# aduinobasic.net
KiCad netlist of a schematic drawn in EAGLE
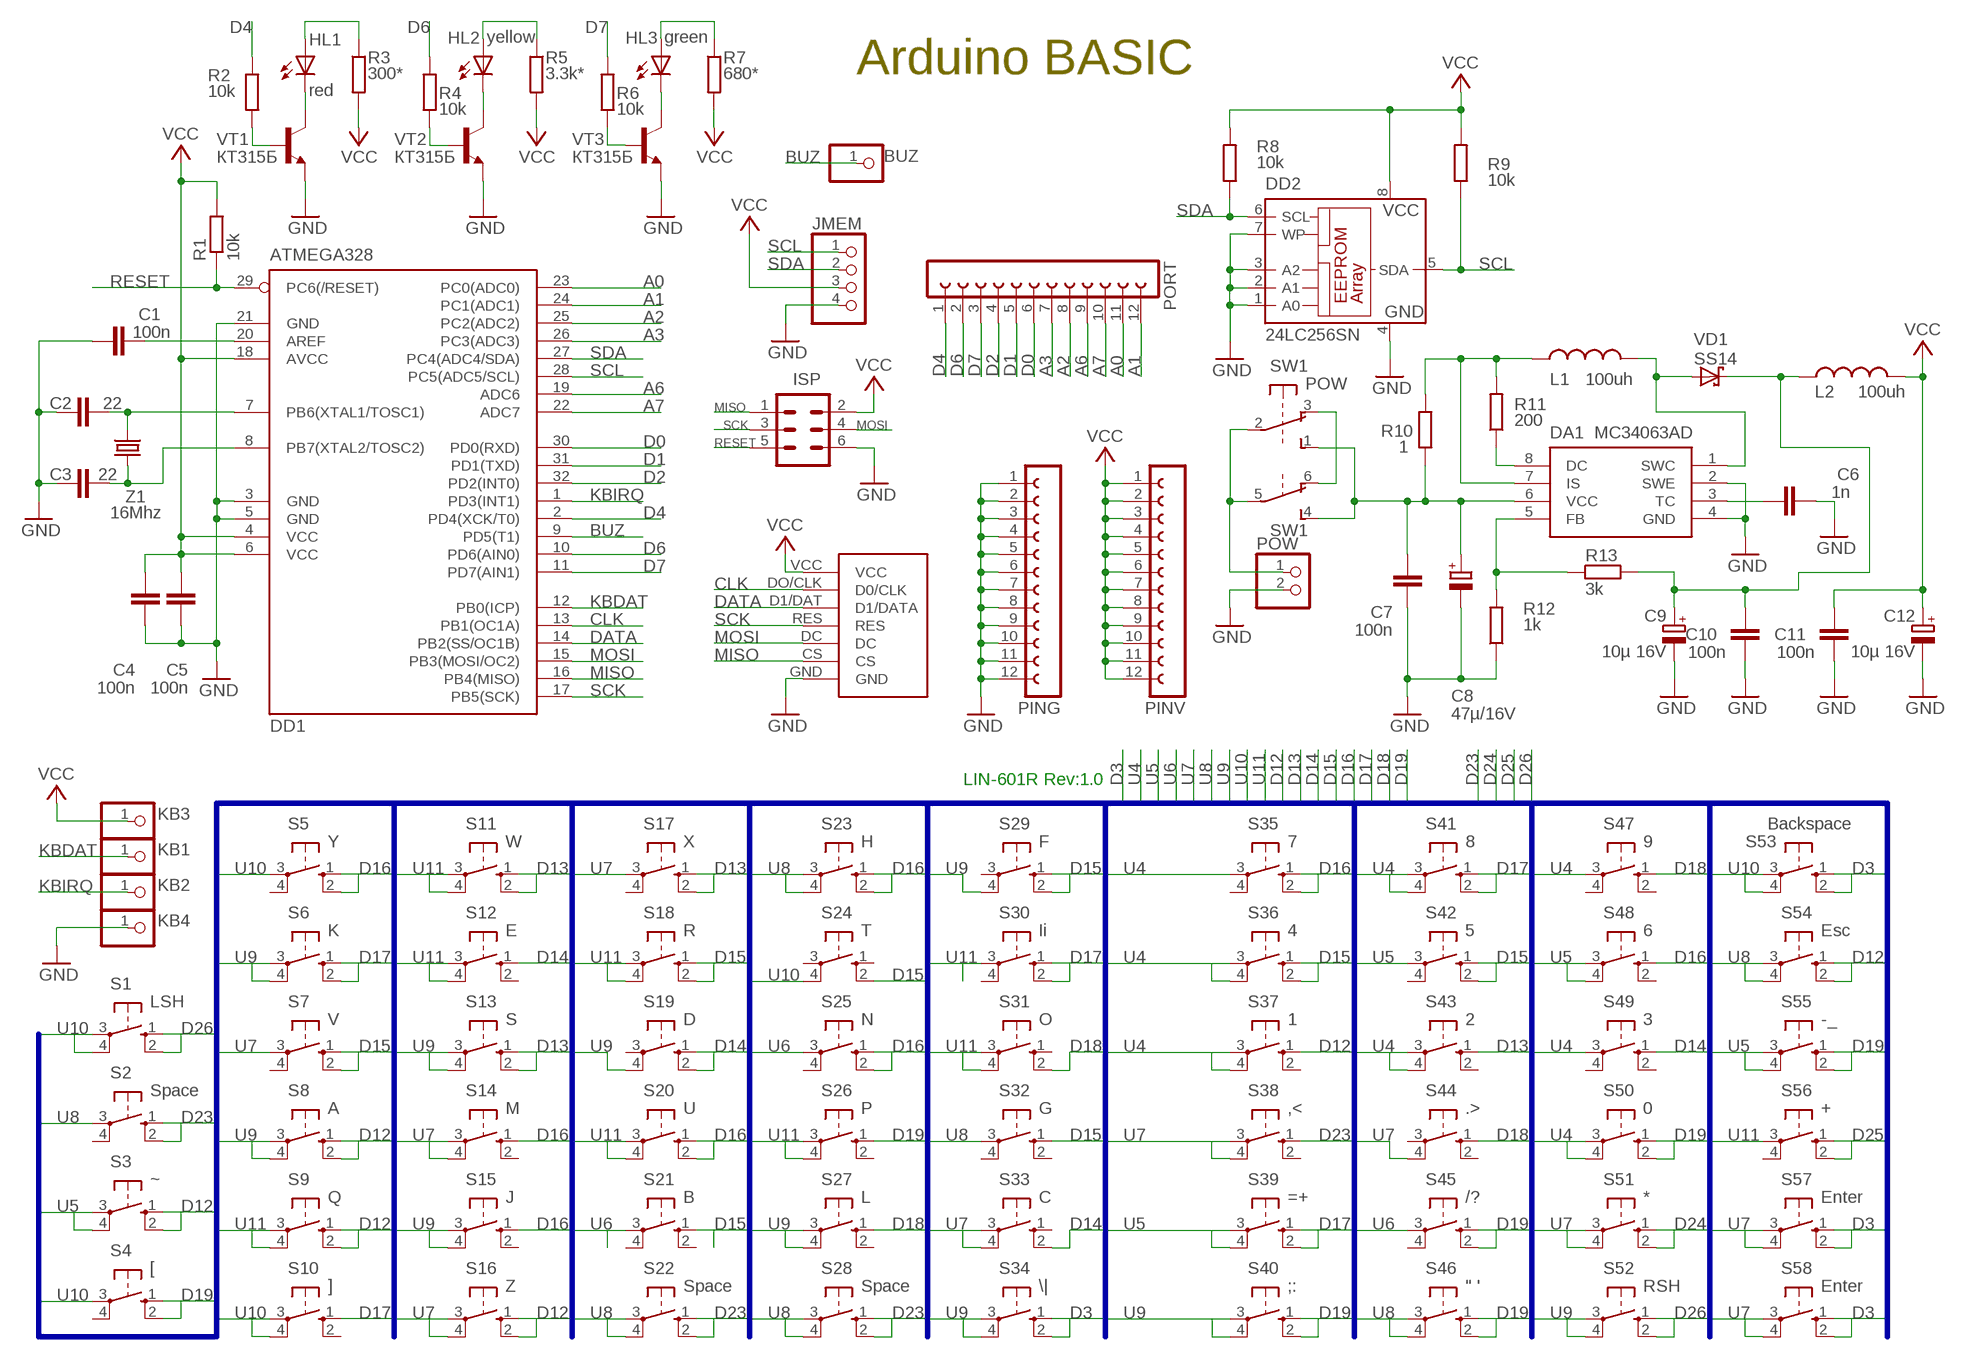
[diagram p0: schematic, sheet 1]

(export (version "E")
  (design (tool "Eeschema 10.0.6"))
  (components
    (comp (ref "BUZ")
      (value "PINHD-1X1")
      (footprint "eagle-import:1X01")
      (libsource (lib "eagle-import") (part "PINHD-1X1"))
    )
    (comp (ref "C1")
      (value "100n")
      (footprint "eagle-import:C0805")
      (libsource (lib "eagle-import") (part "rcl_C-EUC0805"))
    )
    (comp (ref "C2")
      (value "22")
      (footprint "eagle-import:C025-025X050")
      (libsource (lib "eagle-import") (part "rcl_C-EU025-025X050"))
    )
    (comp (ref "C3")
      (value "22")
      (footprint "eagle-import:C025-025X050")
      (libsource (lib "eagle-import") (part "rcl_C-EU025-025X050"))
    )
    (comp (ref "C4")
      (value "100n")
      (footprint "eagle-import:C0805")
      (libsource (lib "eagle-import") (part "rcl_C-EUC0805"))
    )
    (comp (ref "C5")
      (value "100n")
      (footprint "eagle-import:C0805")
      (libsource (lib "eagle-import") (part "rcl_C-EUC0805"))
    )
    (comp (ref "C6")
      (value "1n")
      (footprint "eagle-import:C025-025X050")
      (libsource (lib "eagle-import") (part "rcl_C-EU025-025X050"))
    )
    (comp (ref "C7")
      (value "100n")
      (footprint "eagle-import:C1206")
      (libsource (lib "eagle-import") (part "C-EUC1206"))
    )
    (comp (ref "C8")
      (value "47µ/16V")
      (footprint "eagle-import:RCL_E2-5")
      (libsource (lib "eagle-import") (part "RCL_CPOL-EUE2-5"))
    )
    (comp (ref "C9")
      (value "10µ 16V")
      (footprint "eagle-import:RCL_E2-5")
      (libsource (lib "eagle-import") (part "RCL_CPOL-EUE2-5"))
    )
    (comp (ref "C10")
      (value "100n")
      (footprint "eagle-import:C1206")
      (libsource (lib "eagle-import") (part "rcl_C-EUC1206"))
    )
    (comp (ref "C11")
      (value "100n")
      (footprint "eagle-import:C1206")
      (libsource (lib "eagle-import") (part "rcl_C-EUC1206"))
    )
    (comp (ref "C12")
      (value "10µ 16V")
      (footprint "eagle-import:RCL_E2-5")
      (libsource (lib "eagle-import") (part "RCL_CPOL-EUE2-5"))
    )
    (comp (ref "DA1")
      (value "MC34063AD")
      (footprint "eagle-import:SOIC8")
      (libsource (lib "eagle-import") (part "MC34063AD"))
    )
    (comp (ref "DD1")
      (value "ATMEGA328")
      (footprint "eagle-import:TQFP32-08")
      (fields (field (name "MPN") "ATMEGA8-16AU"))
      (libsource (lib "eagle-import") (part "MEGA8-AI"))
    )
    (comp (ref "DD2")
      (value "24LC256SN")
      (footprint "eagle-import:SO-08")
      (fields (field (name "MF") "MICROCHIP") (field (name "MPN") "24LC256-I/SN"))
      (libsource (lib "eagle-import") (part "24SNLC256"))
    )
    (comp (ref "DISPLAY")
      (value "SSD1306")
      (footprint "eagle-import:SSD1306_0.96")
      (libsource (lib "eagle-import") (part "SSD1306"))
    )
    (comp (ref "HL1")
      (value "red")
      (footprint "eagle-import:LED5MM")
      (libsource (lib "eagle-import") (part "LED5MM"))
    )
    (comp (ref "HL2")
      (value "yellow")
      (footprint "eagle-import:LED5MM")
      (libsource (lib "eagle-import") (part "LED5MM"))
    )
    (comp (ref "HL3")
      (value "green")
      (footprint "eagle-import:LED5MM")
      (libsource (lib "eagle-import") (part "LED5MM"))
    )
    (comp (ref "ISP")
      (value "MA03-2")
      (footprint "eagle-import:MA03-2")
      (libsource (lib "eagle-import") (part "MA03-2"))
    )
    (comp (ref "JMEM")
      (value "PINHD-1X4")
      (footprint "eagle-import:1X04")
      (libsource (lib "eagle-import") (part "PINHD-1X4"))
    )
    (comp (ref "KB1")
      (value "PINHD-1X1")
      (footprint "eagle-import:1X01")
      (libsource (lib "eagle-import") (part "PINHD-1X1"))
    )
    (comp (ref "KB2")
      (value "PINHD-1X1")
      (footprint "eagle-import:1X01")
      (libsource (lib "eagle-import") (part "PINHD-1X1"))
    )
    (comp (ref "KB3")
      (value "PINHD-1X1")
      (footprint "eagle-import:1X01")
      (libsource (lib "eagle-import") (part "PINHD-1X1"))
    )
    (comp (ref "KB4")
      (value "PINHD-1X1")
      (footprint "eagle-import:1X01")
      (libsource (lib "eagle-import") (part "PINHD-1X1"))
    )
    (comp (ref "L1")
      (value "100uh")
      (footprint "eagle-import:0207_10")
      (libsource (lib "eagle-import") (part "L-US0207/10"))
    )
    (comp (ref "L2")
      (value "100uh")
      (footprint "eagle-import:0204_5")
      (libsource (lib "eagle-import") (part "L-US0204/5"))
    )
    (comp (ref "PING")
      (value "FE12-1")
      (footprint "eagle-import:FE12")
      (fields (field (name "OC_FARNELL") "unknown") (field (name "OC_NEWARK") "unknown"))
      (libsource (lib "eagle-import") (part "FE12-1"))
    )
    (comp (ref "PINV")
      (value "FE12-1")
      (footprint "eagle-import:FE12")
      (fields (field (name "OC_FARNELL") "unknown") (field (name "OC_NEWARK") "unknown"))
      (libsource (lib "eagle-import") (part "FE12-1"))
    )
    (comp (ref "PORT")
      (value "FE12-1")
      (footprint "eagle-import:FE12")
      (fields (field (name "OC_FARNELL") "unknown") (field (name "OC_NEWARK") "unknown"))
      (libsource (lib "eagle-import") (part "FE12-1"))
    )
    (comp (ref "POW")
      (value "PINHD-1X2")
      (footprint "eagle-import:1X02")
      (libsource (lib "eagle-import") (part "PINHD-1X2"))
    )
    (comp (ref "R1")
      (value "10k")
      (footprint "eagle-import:R0805")
      (libsource (lib "eagle-import") (part "R-EU_R0805"))
    )
    (comp (ref "R2")
      (value "10k")
      (footprint "eagle-import:R0805")
      (libsource (lib "eagle-import") (part "R-EU_R0805"))
    )
    (comp (ref "R3")
      (value "300*")
      (footprint "eagle-import:R1206W")
      (libsource (lib "eagle-import") (part "R-EU_R1206W"))
    )
    (comp (ref "R4")
      (value "10k")
      (footprint "eagle-import:R0805")
      (libsource (lib "eagle-import") (part "R-EU_R0805"))
    )
    (comp (ref "R5")
      (value "3.3k*")
      (footprint "eagle-import:R1206W")
      (libsource (lib "eagle-import") (part "R-EU_R1206W"))
    )
    (comp (ref "R6")
      (value "10k")
      (footprint "eagle-import:R0805")
      (libsource (lib "eagle-import") (part "R-EU_R0805"))
    )
    (comp (ref "R7")
      (value "680*")
      (footprint "eagle-import:R0805")
      (libsource (lib "eagle-import") (part "R-EU_R0805"))
    )
    (comp (ref "R8")
      (value "10k")
      (footprint "eagle-import:R0805")
      (libsource (lib "eagle-import") (part "R-EU_R0805"))
    )
    (comp (ref "R9")
      (value "10k")
      (footprint "eagle-import:R0805")
      (libsource (lib "eagle-import") (part "R-EU_R0805"))
    )
    (comp (ref "R10")
      (value "1")
      (footprint "eagle-import:M1206")
      (libsource (lib "eagle-import") (part "R-EU_M1206"))
    )
    (comp (ref "R11")
      (value "200")
      (footprint "eagle-import:M1206")
      (libsource (lib "eagle-import") (part "R-EU_M1206"))
    )
    (comp (ref "R12")
      (value "1k")
      (footprint "eagle-import:M0805")
      (libsource (lib "eagle-import") (part "R-EU_M0805"))
    )
    (comp (ref "R13")
      (value "3k")
      (footprint "eagle-import:M0805")
      (libsource (lib "eagle-import") (part "R-EU_M0805"))
    )
    (comp (ref "S1")
      (value "LSH")
      (footprint "eagle-import:B3F-10XX")
      (fields (field (name "MPN") "B3F-1000"))
      (libsource (lib "eagle-import") (part "10-XX"))
    )
    (comp (ref "S2")
      (value "Space")
      (footprint "eagle-import:B3F-10XX")
      (fields (field (name "MPN") "B3F-1000"))
      (libsource (lib "eagle-import") (part "10-XX"))
    )
    (comp (ref "S3")
      (value "~")
      (footprint "eagle-import:B3F-10XX")
      (fields (field (name "MPN") "B3F-1000"))
      (libsource (lib "eagle-import") (part "10-XX"))
    )
    (comp (ref "S4")
      (value "[")
      (footprint "eagle-import:B3F-10XX")
      (fields (field (name "MPN") "B3F-1000"))
      (libsource (lib "eagle-import") (part "10-XX"))
    )
    (comp (ref "S5")
      (value "Y")
      (footprint "eagle-import:B3F-10XX")
      (fields (field (name "MPN") "B3F-1000"))
      (libsource (lib "eagle-import") (part "10-XX"))
    )
    (comp (ref "S6")
      (value "K")
      (footprint "eagle-import:B3F-10XX")
      (fields (field (name "MPN") "B3F-1000"))
      (libsource (lib "eagle-import") (part "10-XX"))
    )
    (comp (ref "S7")
      (value "V")
      (footprint "eagle-import:B3F-10XX")
      (fields (field (name "MPN") "B3F-1000"))
      (libsource (lib "eagle-import") (part "10-XX"))
    )
    (comp (ref "S8")
      (value "A")
      (footprint "eagle-import:B3F-10XX")
      (fields (field (name "MPN") "B3F-1000"))
      (libsource (lib "eagle-import") (part "10-XX"))
    )
    (comp (ref "S9")
      (value "Q")
      (footprint "eagle-import:B3F-10XX")
      (fields (field (name "MPN") "B3F-1000"))
      (libsource (lib "eagle-import") (part "10-XX"))
    )
    (comp (ref "S10")
      (value "]")
      (footprint "eagle-import:B3F-10XX")
      (fields (field (name "MPN") "B3F-1000"))
      (libsource (lib "eagle-import") (part "10-XX"))
    )
    (comp (ref "S11")
      (value "W")
      (footprint "eagle-import:B3F-10XX")
      (fields (field (name "MPN") "B3F-1000"))
      (libsource (lib "eagle-import") (part "10-XX"))
    )
    (comp (ref "S12")
      (value "E")
      (footprint "eagle-import:B3F-10XX")
      (fields (field (name "MPN") "B3F-1000"))
      (libsource (lib "eagle-import") (part "10-XX"))
    )
    (comp (ref "S13")
      (value "S")
      (footprint "eagle-import:B3F-10XX")
      (fields (field (name "MPN") "B3F-1000"))
      (libsource (lib "eagle-import") (part "10-XX"))
    )
    (comp (ref "S14")
      (value "M")
      (footprint "eagle-import:B3F-10XX")
      (fields (field (name "MPN") "B3F-1000"))
      (libsource (lib "eagle-import") (part "10-XX"))
    )
    (comp (ref "S15")
      (value "J")
      (footprint "eagle-import:B3F-10XX")
      (fields (field (name "MPN") "B3F-1000"))
      (libsource (lib "eagle-import") (part "10-XX"))
    )
    (comp (ref "S16")
      (value "Z")
      (footprint "eagle-import:B3F-10XX")
      (fields (field (name "MPN") "B3F-1000"))
      (libsource (lib "eagle-import") (part "10-XX"))
    )
    (comp (ref "S17")
      (value "X")
      (footprint "eagle-import:B3F-10XX")
      (fields (field (name "MPN") "B3F-1000"))
      (libsource (lib "eagle-import") (part "10-XX"))
    )
    (comp (ref "S18")
      (value "R")
      (footprint "eagle-import:B3F-10XX")
      (fields (field (name "MPN") "B3F-1000"))
      (libsource (lib "eagle-import") (part "10-XX"))
    )
    (comp (ref "S19")
      (value "D")
      (footprint "eagle-import:B3F-10XX")
      (fields (field (name "MPN") "B3F-1000"))
      (libsource (lib "eagle-import") (part "10-XX"))
    )
    (comp (ref "S20")
      (value "U")
      (footprint "eagle-import:B3F-10XX")
      (fields (field (name "MPN") "B3F-1000"))
      (libsource (lib "eagle-import") (part "10-XX"))
    )
    (comp (ref "S21")
      (value "B")
      (footprint "eagle-import:B3F-10XX")
      (fields (field (name "MPN") "B3F-1000"))
      (libsource (lib "eagle-import") (part "10-XX"))
    )
    (comp (ref "S22")
      (value "Space")
      (footprint "eagle-import:B3F-10XX")
      (fields (field (name "MPN") "B3F-1000"))
      (libsource (lib "eagle-import") (part "10-XX"))
    )
    (comp (ref "S23")
      (value "H")
      (footprint "eagle-import:B3F-10XX")
      (fields (field (name "MPN") "B3F-1000"))
      (libsource (lib "eagle-import") (part "10-XX"))
    )
    (comp (ref "S24")
      (value "T")
      (footprint "eagle-import:B3F-10XX")
      (fields (field (name "MPN") "B3F-1000"))
      (libsource (lib "eagle-import") (part "10-XX"))
    )
    (comp (ref "S25")
      (value "N")
      (footprint "eagle-import:B3F-10XX")
      (fields (field (name "MPN") "B3F-1000"))
      (libsource (lib "eagle-import") (part "10-XX"))
    )
    (comp (ref "S26")
      (value "P")
      (footprint "eagle-import:B3F-10XX")
      (fields (field (name "MPN") "B3F-1000"))
      (libsource (lib "eagle-import") (part "10-XX"))
    )
    (comp (ref "S27")
      (value "L")
      (footprint "eagle-import:B3F-10XX")
      (fields (field (name "MPN") "B3F-1000"))
      (libsource (lib "eagle-import") (part "10-XX"))
    )
    (comp (ref "S28")
      (value "Space")
      (footprint "eagle-import:B3F-10XX")
      (fields (field (name "MPN") "B3F-1000"))
      (libsource (lib "eagle-import") (part "10-XX"))
    )
    (comp (ref "S29")
      (value "F")
      (footprint "eagle-import:B3F-10XX")
      (fields (field (name "MPN") "B3F-1000"))
      (libsource (lib "eagle-import") (part "10-XX"))
    )
    (comp (ref "S30")
      (value "Ii")
      (footprint "eagle-import:B3F-10XX")
      (fields (field (name "MPN") "B3F-1000"))
      (libsource (lib "eagle-import") (part "10-XX"))
    )
    (comp (ref "S31")
      (value "O")
      (footprint "eagle-import:B3F-10XX")
      (fields (field (name "MPN") "B3F-1000"))
      (libsource (lib "eagle-import") (part "10-XX"))
    )
    (comp (ref "S32")
      (value "G")
      (footprint "eagle-import:B3F-10XX")
      (fields (field (name "MPN") "B3F-1000"))
      (libsource (lib "eagle-import") (part "10-XX"))
    )
    (comp (ref "S33")
      (value "C")
      (footprint "eagle-import:B3F-10XX")
      (fields (field (name "MPN") "B3F-1000"))
      (libsource (lib "eagle-import") (part "10-XX"))
    )
    (comp (ref "S34")
      (value "\\|")
      (footprint "eagle-import:B3F-10XX")
      (fields (field (name "MPN") "B3F-1000"))
      (libsource (lib "eagle-import") (part "10-XX"))
    )
    (comp (ref "S35")
      (value "7")
      (footprint "eagle-import:B3F-10XX")
      (fields (field (name "MPN") "B3F-1000"))
      (libsource (lib "eagle-import") (part "10-XX"))
    )
    (comp (ref "S36")
      (value "4")
      (footprint "eagle-import:B3F-10XX")
      (fields (field (name "MPN") "B3F-1000"))
      (libsource (lib "eagle-import") (part "10-XX"))
    )
    (comp (ref "S37")
      (value "1")
      (footprint "eagle-import:B3F-10XX")
      (fields (field (name "MPN") "B3F-1000"))
      (libsource (lib "eagle-import") (part "10-XX"))
    )
    (comp (ref "S38")
      (value ",<")
      (footprint "eagle-import:B3F-10XX")
      (fields (field (name "MPN") "B3F-1000"))
      (libsource (lib "eagle-import") (part "10-XX"))
    )
    (comp (ref "S39")
      (value "=+")
      (footprint "eagle-import:B3F-10XX")
      (fields (field (name "MPN") "B3F-1000"))
      (libsource (lib "eagle-import") (part "10-XX"))
    )
    (comp (ref "S40")
      (value ";:")
      (footprint "eagle-import:B3F-10XX")
      (fields (field (name "MPN") "B3F-1000"))
      (libsource (lib "eagle-import") (part "10-XX"))
    )
    (comp (ref "S41")
      (value "8")
      (footprint "eagle-import:B3F-10XX")
      (fields (field (name "MPN") "B3F-1000"))
      (libsource (lib "eagle-import") (part "10-XX"))
    )
    (comp (ref "S42")
      (value "5")
      (footprint "eagle-import:B3F-10XX")
      (fields (field (name "MPN") "B3F-1000"))
      (libsource (lib "eagle-import") (part "10-XX"))
    )
    (comp (ref "S43")
      (value "2")
      (footprint "eagle-import:B3F-10XX")
      (fields (field (name "MPN") "B3F-1000"))
      (libsource (lib "eagle-import") (part "10-XX"))
    )
    (comp (ref "S44")
      (value ".>")
      (footprint "eagle-import:B3F-10XX")
      (fields (field (name "MPN") "B3F-1000"))
      (libsource (lib "eagle-import") (part "10-XX"))
    )
    (comp (ref "S45")
      (value "/?")
      (footprint "eagle-import:B3F-10XX")
      (fields (field (name "MPN") "B3F-1000"))
      (libsource (lib "eagle-import") (part "10-XX"))
    )
    (comp (ref "S46")
      (value "\" '")
      (footprint "eagle-import:B3F-10XX")
      (fields (field (name "MPN") "B3F-1000"))
      (libsource (lib "eagle-import") (part "10-XX"))
    )
    (comp (ref "S47")
      (value "9")
      (footprint "eagle-import:B3F-10XX")
      (fields (field (name "MPN") "B3F-1000"))
      (libsource (lib "eagle-import") (part "10-XX"))
    )
    (comp (ref "S48")
      (value "6")
      (footprint "eagle-import:B3F-10XX")
      (fields (field (name "MPN") "B3F-1000"))
      (libsource (lib "eagle-import") (part "10-XX"))
    )
    (comp (ref "S49")
      (value "3")
      (footprint "eagle-import:B3F-10XX")
      (fields (field (name "MPN") "B3F-1000"))
      (libsource (lib "eagle-import") (part "10-XX"))
    )
    (comp (ref "S50")
      (value "0")
      (footprint "eagle-import:B3F-10XX")
      (fields (field (name "MPN") "B3F-1000"))
      (libsource (lib "eagle-import") (part "10-XX"))
    )
    (comp (ref "S51")
      (value "*")
      (footprint "eagle-import:B3F-10XX")
      (fields (field (name "MPN") "B3F-1000"))
      (libsource (lib "eagle-import") (part "10-XX"))
    )
    (comp (ref "S52")
      (value "RSH")
      (footprint "eagle-import:B3F-10XX")
      (fields (field (name "MPN") "B3F-1000"))
      (libsource (lib "eagle-import") (part "10-XX"))
    )
    (comp (ref "S53")
      (value "Backspace")
      (footprint "eagle-import:B3F-10XX")
      (fields (field (name "MPN") "B3F-1000"))
      (libsource (lib "eagle-import") (part "10-XX"))
    )
    (comp (ref "S54")
      (value "Esc")
      (footprint "eagle-import:B3F-10XX")
      (fields (field (name "MPN") "B3F-1000"))
      (libsource (lib "eagle-import") (part "10-XX"))
    )
    (comp (ref "S55")
      (value "-_")
      (footprint "eagle-import:B3F-10XX")
      (fields (field (name "MPN") "B3F-1000"))
      (libsource (lib "eagle-import") (part "10-XX"))
    )
    (comp (ref "S56")
      (value "+")
      (footprint "eagle-import:B3F-10XX")
      (fields (field (name "MPN") "B3F-1000"))
      (libsource (lib "eagle-import") (part "10-XX"))
    )
    (comp (ref "S57")
      (value "Enter")
      (footprint "eagle-import:B3F-10XX")
      (fields (field (name "MPN") "B3F-1000"))
      (libsource (lib "eagle-import") (part "10-XX"))
    )
    (comp (ref "S58")
      (value "Enter")
      (footprint "eagle-import:B3F-10XX")
      (fields (field (name "MPN") "B3F-1000"))
      (libsource (lib "eagle-import") (part "10-XX"))
    )
    (comp (ref "SW1")
      (value "POW")
      (footprint "eagle-import:9077-2")
      (libsource (lib "eagle-import") (part "9077-2"))
    )
    (comp (ref "VD1")
      (value "SS14")
      (footprint "eagle-import:SMB")
      (libsource (lib "eagle-import") (part "SCHOTTKY-DIODESMD"))
    )
    (comp (ref "VT1")
      (value "КТ315Б")
      (footprint "eagle-import:TO92-ECB")
      (libsource (lib "eagle-import") (part "-NPN-TO92-ECBBC368"))
    )
    (comp (ref "VT2")
      (value "КТ315Б")
      (footprint "eagle-import:TO92-ECB")
      (libsource (lib "eagle-import") (part "-NPN-TO92-ECBBC368"))
    )
    (comp (ref "VT3")
      (value "КТ315Б")
      (footprint "eagle-import:TO92-ECB")
      (libsource (lib "eagle-import") (part "-NPN-TO92-ECBBC368"))
    )
    (comp (ref "Z1")
      (value "16Mhz")
      (footprint "eagle-import:HC49_S")
      (libsource (lib "eagle-import") (part "CRYSTALHC49S"))
    )
  )
  (nets
    (net (code "2") (name "A0") (class "Default")
      (node (ref "DD1") (pin "23") (pinfunction "PC0(ADC0)_23") (pintype "bidirectional"))
      (node (ref "PORT") (pin "11") (pinfunction "11_11") (pintype "passive"))
    )
    (net (code "3") (name "A1") (class "Default")
      (node (ref "DD1") (pin "24") (pinfunction "PC1(ADC1)_24") (pintype "bidirectional"))
      (node (ref "PORT") (pin "12") (pinfunction "12_12") (pintype "passive"))
    )
    (net (code "4") (name "A2") (class "Default")
      (node (ref "DD1") (pin "25") (pinfunction "PC2(ADC2)_25") (pintype "bidirectional"))
      (node (ref "PORT") (pin "8") (pinfunction "8_8") (pintype "passive"))
    )
    (net (code "5") (name "A3") (class "Default")
      (node (ref "DD1") (pin "26") (pinfunction "PC3(ADC3)_26") (pintype "bidirectional"))
      (node (ref "PORT") (pin "7") (pinfunction "7_7") (pintype "passive"))
    )
    (net (code "6") (name "A6") (class "Default")
      (node (ref "DD1") (pin "19") (pinfunction "ADC6_19") (pintype "bidirectional"))
      (node (ref "PORT") (pin "9") (pinfunction "9_9") (pintype "passive"))
    )
    (net (code "7") (name "A7") (class "Default")
      (node (ref "DD1") (pin "22") (pinfunction "ADC7_22") (pintype "bidirectional"))
      (node (ref "PORT") (pin "10") (pinfunction "10_10") (pintype "passive"))
    )
    (net (code "8") (name "BUZ") (class "Default")
      (node (ref "BUZ") (pin "1") (pinfunction "1_1") (pintype "passive"))
      (node (ref "DD1") (pin "9") (pinfunction "PD5(T1)_9") (pintype "bidirectional"))
    )
    (net (code "9") (name "CLK") (class "Default")
      (node (ref "DD1") (pin "13") (pinfunction "PB1(OC1A)_13") (pintype "bidirectional"))
      (node (ref "DISPLAY") (pin "DO/CLK") (pinfunction "D0/CLK_DO/CLK") (pintype "bidirectional"))
    )
    (net (code "10") (name "D0") (class "Default")
      (node (ref "DD1") (pin "30") (pinfunction "PD0(RXD)_30") (pintype "bidirectional"))
      (node (ref "PORT") (pin "6") (pinfunction "6_6") (pintype "passive"))
    )
    (net (code "11") (name "D1") (class "Default")
      (node (ref "DD1") (pin "31") (pinfunction "PD1(TXD)_31") (pintype "bidirectional"))
      (node (ref "PORT") (pin "5") (pinfunction "5_5") (pintype "passive"))
    )
    (net (code "12") (name "D2") (class "Default")
      (node (ref "DD1") (pin "32") (pinfunction "PD2(INT0)_32") (pintype "bidirectional"))
      (node (ref "PORT") (pin "4") (pinfunction "4_4") (pintype "passive"))
    )
    (net (code "13") (name "D3") (class "Default")
      (node (ref "S34") (pin "1") (pinfunction "S_1") (pintype "passive"))
      (node (ref "S34") (pin "2") (pinfunction "S1_2") (pintype "passive"))
      (node (ref "S53") (pin "1") (pinfunction "S_1") (pintype "passive"))
      (node (ref "S53") (pin "2") (pinfunction "S1_2") (pintype "passive"))
      (node (ref "S57") (pin "1") (pinfunction "S_1") (pintype "passive"))
      (node (ref "S57") (pin "2") (pinfunction "S1_2") (pintype "passive"))
      (node (ref "S58") (pin "1") (pinfunction "S_1") (pintype "passive"))
      (node (ref "S58") (pin "2") (pinfunction "S1_2") (pintype "passive"))
    )
    (net (code "14") (name "D4") (class "Default")
      (node (ref "DD1") (pin "2") (pinfunction "PD4(XCK/T0)_2") (pintype "bidirectional"))
      (node (ref "PORT") (pin "1") (pinfunction "1_1") (pintype "passive"))
      (node (ref "R2") (pin "1") (pinfunction "1_1") (pintype "passive"))
    )
    (net (code "15") (name "D6") (class "Default")
      (node (ref "DD1") (pin "10") (pinfunction "PD6(AIN0)_10") (pintype "bidirectional"))
      (node (ref "PORT") (pin "2") (pinfunction "2_2") (pintype "passive"))
      (node (ref "R4") (pin "1") (pinfunction "1_1") (pintype "passive"))
    )
    (net (code "16") (name "D7") (class "Default")
      (node (ref "DD1") (pin "11") (pinfunction "PD7(AIN1)_11") (pintype "bidirectional"))
      (node (ref "PORT") (pin "3") (pinfunction "3_3") (pintype "passive"))
      (node (ref "R6") (pin "1") (pinfunction "1_1") (pintype "passive"))
    )
    (net (code "17") (name "D12") (class "Default")
      (node (ref "S16") (pin "1") (pinfunction "S_1") (pintype "passive"))
      (node (ref "S16") (pin "2") (pinfunction "S1_2") (pintype "passive"))
      (node (ref "S3") (pin "1") (pinfunction "S_1") (pintype "passive"))
      (node (ref "S3") (pin "2") (pinfunction "S1_2") (pintype "passive"))
      (node (ref "S37") (pin "1") (pinfunction "S_1") (pintype "passive"))
      (node (ref "S54") (pin "1") (pinfunction "S_1") (pintype "passive"))
      (node (ref "S54") (pin "2") (pinfunction "S1_2") (pintype "passive"))
      (node (ref "S8") (pin "1") (pinfunction "S_1") (pintype "passive"))
      (node (ref "S8") (pin "2") (pinfunction "S1_2") (pintype "passive"))
      (node (ref "S9") (pin "1") (pinfunction "S_1") (pintype "passive"))
      (node (ref "S9") (pin "2") (pinfunction "S1_2") (pintype "passive"))
    )
    (net (code "18") (name "D13") (class "Default")
      (node (ref "S11") (pin "1") (pinfunction "S_1") (pintype "passive"))
      (node (ref "S11") (pin "2") (pinfunction "S1_2") (pintype "passive"))
      (node (ref "S13") (pin "1") (pinfunction "S_1") (pintype "passive"))
      (node (ref "S13") (pin "2") (pinfunction "S1_2") (pintype "passive"))
      (node (ref "S17") (pin "1") (pinfunction "S_1") (pintype "passive"))
      (node (ref "S17") (pin "2") (pinfunction "S1_2") (pintype "passive"))
      (node (ref "S43") (pin "1") (pinfunction "S_1") (pintype "passive"))
    )
    (net (code "19") (name "D14") (class "Default")
      (node (ref "S12") (pin "1") (pinfunction "S_1") (pintype "passive"))
      (node (ref "S19") (pin "1") (pinfunction "S_1") (pintype "passive"))
      (node (ref "S19") (pin "2") (pinfunction "S1_2") (pintype "passive"))
      (node (ref "S33") (pin "2") (pinfunction "S1_2") (pintype "passive"))
      (node (ref "S49") (pin "1") (pinfunction "S_1") (pintype "passive"))
    )
    (net (code "20") (name "D15") (class "Default")
      (node (ref "S18") (pin "1") (pinfunction "S_1") (pintype "passive"))
      (node (ref "S18") (pin "2") (pinfunction "S1_2") (pintype "passive"))
      (node (ref "S21") (pin "1") (pinfunction "S_1") (pintype "passive"))
      (node (ref "S24") (pin "2") (pinfunction "S1_2") (pintype "passive"))
      (node (ref "S29") (pin "1") (pinfunction "S_1") (pintype "passive"))
      (node (ref "S29") (pin "2") (pinfunction "S1_2") (pintype "passive"))
      (node (ref "S32") (pin "1") (pinfunction "S_1") (pintype "passive"))
      (node (ref "S36") (pin "1") (pinfunction "S_1") (pintype "passive"))
      (node (ref "S36") (pin "2") (pinfunction "S1_2") (pintype "passive"))
      (node (ref "S42") (pin "1") (pinfunction "S_1") (pintype "passive"))
      (node (ref "S42") (pin "2") (pinfunction "S1_2") (pintype "passive"))
      (node (ref "S7") (pin "1") (pinfunction "S_1") (pintype "passive"))
      (node (ref "S7") (pin "2") (pinfunction "S1_2") (pintype "passive"))
    )
    (net (code "21") (name "D16") (class "Default")
      (node (ref "S14") (pin "1") (pinfunction "S_1") (pintype "passive"))
      (node (ref "S15") (pin "1") (pinfunction "S_1") (pintype "passive"))
      (node (ref "S20") (pin "1") (pinfunction "S_1") (pintype "passive"))
      (node (ref "S20") (pin "2") (pinfunction "S1_2") (pintype "passive"))
      (node (ref "S23") (pin "1") (pinfunction "S_1") (pintype "passive"))
      (node (ref "S23") (pin "2") (pinfunction "S1_2") (pintype "passive"))
      (node (ref "S25") (pin "1") (pinfunction "S_1") (pintype "passive"))
      (node (ref "S25") (pin "2") (pinfunction "S1_2") (pintype "passive"))
      (node (ref "S35") (pin "1") (pinfunction "S_1") (pintype "passive"))
      (node (ref "S35") (pin "2") (pinfunction "S1_2") (pintype "passive"))
      (node (ref "S48") (pin "1") (pinfunction "S_1") (pintype "passive"))
      (node (ref "S5") (pin "1") (pinfunction "S_1") (pintype "passive"))
      (node (ref "S5") (pin "2") (pinfunction "S1_2") (pintype "passive"))
    )
    (net (code "22") (name "D17") (class "Default")
      (node (ref "S10") (pin "1") (pinfunction "S_1") (pintype "passive"))
      (node (ref "S30") (pin "1") (pinfunction "S_1") (pintype "passive"))
      (node (ref "S30") (pin "2") (pinfunction "S1_2") (pintype "passive"))
      (node (ref "S39") (pin "1") (pinfunction "S_1") (pintype "passive"))
      (node (ref "S39") (pin "2") (pinfunction "S1_2") (pintype "passive"))
      (node (ref "S41") (pin "1") (pinfunction "S_1") (pintype "passive"))
      (node (ref "S41") (pin "2") (pinfunction "S1_2") (pintype "passive"))
      (node (ref "S6") (pin "1") (pinfunction "S_1") (pintype "passive"))
      (node (ref "S6") (pin "2") (pinfunction "S1_2") (pintype "passive"))
    )
    (net (code "23") (name "D18") (class "Default")
      (node (ref "S27") (pin "1") (pinfunction "S_1") (pintype "passive"))
      (node (ref "S31") (pin "2") (pinfunction "S1_2") (pintype "passive"))
      (node (ref "S44") (pin "1") (pinfunction "S_1") (pintype "passive"))
      (node (ref "S47") (pin "1") (pinfunction "S_1") (pintype "passive"))
    )
    (net (code "24") (name "D19") (class "Default")
      (node (ref "S26") (pin "1") (pinfunction "S_1") (pintype "passive"))
      (node (ref "S4") (pin "1") (pinfunction "S_1") (pintype "passive"))
      (node (ref "S4") (pin "2") (pinfunction "S1_2") (pintype "passive"))
      (node (ref "S40") (pin "1") (pinfunction "S_1") (pintype "passive"))
      (node (ref "S40") (pin "2") (pinfunction "S1_2") (pintype "passive"))
      (node (ref "S45") (pin "1") (pinfunction "S_1") (pintype "passive"))
      (node (ref "S45") (pin "2") (pinfunction "S1_2") (pintype "passive"))
      (node (ref "S46") (pin "1") (pinfunction "S_1") (pintype "passive"))
      (node (ref "S46") (pin "2") (pinfunction "S1_2") (pintype "passive"))
      (node (ref "S50") (pin "1") (pinfunction "S_1") (pintype "passive"))
      (node (ref "S50") (pin "2") (pinfunction "S1_2") (pintype "passive"))
      (node (ref "S55") (pin "1") (pinfunction "S_1") (pintype "passive"))
      (node (ref "S55") (pin "2") (pinfunction "S1_2") (pintype "passive"))
    )
    (net (code "25") (name "D23") (class "Default")
      (node (ref "S2") (pin "1") (pinfunction "S_1") (pintype "passive"))
      (node (ref "S2") (pin "2") (pinfunction "S1_2") (pintype "passive"))
      (node (ref "S22") (pin "1") (pinfunction "S_1") (pintype "passive"))
      (node (ref "S22") (pin "2") (pinfunction "S1_2") (pintype "passive"))
      (node (ref "S28") (pin "1") (pinfunction "S_1") (pintype "passive"))
      (node (ref "S28") (pin "2") (pinfunction "S1_2") (pintype "passive"))
      (node (ref "S38") (pin "1") (pinfunction "S_1") (pintype "passive"))
    )
    (net (code "26") (name "D24") (class "Default")
      (node (ref "S51") (pin "1") (pinfunction "S_1") (pintype "passive"))
      (node (ref "S51") (pin "2") (pinfunction "S1_2") (pintype "passive"))
    )
    (net (code "27") (name "D25") (class "Default")
      (node (ref "S56") (pin "1") (pinfunction "S_1") (pintype "passive"))
      (node (ref "S56") (pin "2") (pinfunction "S1_2") (pintype "passive"))
    )
    (net (code "28") (name "D26") (class "Default")
      (node (ref "S1") (pin "1") (pinfunction "S_1") (pintype "passive"))
      (node (ref "S1") (pin "2") (pinfunction "S1_2") (pintype "passive"))
      (node (ref "S52") (pin "1") (pinfunction "S_1") (pintype "passive"))
      (node (ref "S52") (pin "2") (pinfunction "S1_2") (pintype "passive"))
    )
    (net (code "29") (name "DATA") (class "Default")
      (node (ref "DD1") (pin "14") (pinfunction "PB2(SS/OC1B)_14") (pintype "bidirectional"))
      (node (ref "DISPLAY") (pin "D1/DAT") (pinfunction "D1/DATA_D1/DAT") (pintype "bidirectional"))
    )
    (net (code "30") (name "GND") (class "Default")
      (node (ref "C1") (pin "1") (pinfunction "1_1") (pintype "passive"))
      (node (ref "C10") (pin "1") (pinfunction "1_1") (pintype "passive"))
      (node (ref "C11") (pin "1") (pinfunction "1_1") (pintype "passive"))
      (node (ref "C12") (pin "-") (pinfunction "-_-") (pintype "passive"))
      (node (ref "C2") (pin "1") (pinfunction "1_1") (pintype "passive"))
      (node (ref "C3") (pin "1") (pinfunction "1_1") (pintype "passive"))
      (node (ref "C4") (pin "2") (pinfunction "2_2") (pintype "passive"))
      (node (ref "C5") (pin "2") (pinfunction "2_2") (pintype "passive"))
      (node (ref "C6") (pin "2") (pinfunction "2_2") (pintype "passive"))
      (node (ref "C7") (pin "2") (pinfunction "2_2") (pintype "passive"))
      (node (ref "C8") (pin "-") (pinfunction "-_-") (pintype "passive"))
      (node (ref "C9") (pin "-") (pinfunction "-_-") (pintype "passive"))
      (node (ref "DA1") (pin "2") (pinfunction "SWE_2") (pintype "passive"))
      (node (ref "DA1") (pin "4") (pinfunction "GND_4") (pintype "passive"))
      (node (ref "DD1") (pin "21") (pinfunction "GND_21") (pintype "power_in"))
      (node (ref "DD1") (pin "3") (pinfunction "GND_3") (pintype "power_in"))
      (node (ref "DD1") (pin "5") (pinfunction "GND_5") (pintype "power_in"))
      (node (ref "DD2") (pin "1") (pinfunction "A0_1") (pintype "input"))
      (node (ref "DD2") (pin "2") (pinfunction "A1_2") (pintype "input"))
      (node (ref "DD2") (pin "3") (pinfunction "A2_3") (pintype "input"))
      (node (ref "DD2") (pin "4") (pinfunction "GND_4") (pintype "power_in"))
      (node (ref "DD2") (pin "7") (pinfunction "WP_7") (pintype "input"))
      (node (ref "DISPLAY") (pin "GND") (pinfunction "GND_GND") (pintype "bidirectional"))
      (node (ref "ISP") (pin "6") (pinfunction "6_6") (pintype "passive"))
      (node (ref "JMEM") (pin "4") (pinfunction "4_4") (pintype "passive"))
      (node (ref "KB4") (pin "1") (pinfunction "1_1") (pintype "passive"))
      (node (ref "PING") (pin "1") (pinfunction "1_1") (pintype "passive"))
      (node (ref "PING") (pin "10") (pinfunction "10_10") (pintype "passive"))
      (node (ref "PING") (pin "11") (pinfunction "11_11") (pintype "passive"))
      (node (ref "PING") (pin "12") (pinfunction "12_12") (pintype "passive"))
      (node (ref "PING") (pin "2") (pinfunction "2_2") (pintype "passive"))
      (node (ref "PING") (pin "3") (pinfunction "3_3") (pintype "passive"))
      (node (ref "PING") (pin "4") (pinfunction "4_4") (pintype "passive"))
      (node (ref "PING") (pin "5") (pinfunction "5_5") (pintype "passive"))
      (node (ref "PING") (pin "6") (pinfunction "6_6") (pintype "passive"))
      (node (ref "PING") (pin "7") (pinfunction "7_7") (pintype "passive"))
      (node (ref "PING") (pin "8") (pinfunction "8_8") (pintype "passive"))
      (node (ref "PING") (pin "9") (pinfunction "9_9") (pintype "passive"))
      (node (ref "POW") (pin "2") (pinfunction "2_2") (pintype "passive"))
      (node (ref "R12") (pin "1") (pinfunction "1_1") (pintype "passive"))
      (node (ref "VT1") (pin "E") (pinfunction "E_E") (pintype "passive"))
      (node (ref "VT2") (pin "E") (pinfunction "E_E") (pintype "passive"))
      (node (ref "VT3") (pin "E") (pinfunction "E_E") (pintype "passive"))
    )
    (net (code "31") (name "KBDAT") (class "Default")
      (node (ref "DD1") (pin "12") (pinfunction "PB0(ICP)_12") (pintype "bidirectional"))
      (node (ref "KB1") (pin "1") (pinfunction "1_1") (pintype "passive"))
    )
    (net (code "32") (name "KBIRQ") (class "Default")
      (node (ref "DD1") (pin "1") (pinfunction "PD3(INT1)_1") (pintype "bidirectional"))
      (node (ref "KB2") (pin "1") (pinfunction "1_1") (pintype "passive"))
    )
    (net (code "33") (name "MISO") (class "Default")
      (node (ref "DD1") (pin "16") (pinfunction "PB4(MISO)_16") (pintype "bidirectional"))
      (node (ref "DISPLAY") (pin "CS") (pinfunction "CS_CS") (pintype "bidirectional"))
      (node (ref "ISP") (pin "1") (pinfunction "1_1") (pintype "passive"))
    )
    (net (code "34") (name "MOSI") (class "Default")
      (node (ref "DD1") (pin "15") (pinfunction "PB3(MOSI/OC2)_15") (pintype "bidirectional"))
      (node (ref "DISPLAY") (pin "DC") (pinfunction "DC_DC") (pintype "bidirectional"))
      (node (ref "ISP") (pin "4") (pinfunction "4_4") (pintype "passive"))
    )
    (net (code "35") (name "Net-(C10-Pad2)") (class "Default")
      (node (ref "C10") (pin "2") (pinfunction "2_2") (pintype "passive"))
      (node (ref "C9") (pin "+") (pinfunction "+_+") (pintype "passive"))
      (node (ref "L2") (pin "1") (pinfunction "1_1") (pintype "passive"))
      (node (ref "R13") (pin "2") (pinfunction "2_2") (pintype "passive"))
      (node (ref "VD1") (pin "C") (pinfunction "C_C") (pintype "passive"))
    )
    (net (code "36") (name "Net-(DA1-DC)") (class "Default")
      (node (ref "DA1") (pin "8") (pinfunction "DC_8") (pintype "passive"))
      (node (ref "R11") (pin "1") (pinfunction "1_1") (pintype "passive"))
    )
    (net (code "37") (name "Net-(DA1-FB)") (class "Default")
      (node (ref "DA1") (pin "5") (pinfunction "FB_5") (pintype "passive"))
      (node (ref "R12") (pin "2") (pinfunction "2_2") (pintype "passive"))
      (node (ref "R13") (pin "1") (pinfunction "1_1") (pintype "passive"))
    )
    (net (code "38") (name "Net-(DA1-IS)") (class "Default")
      (node (ref "DA1") (pin "7") (pinfunction "IS_7") (pintype "passive"))
      (node (ref "L1") (pin "1") (pinfunction "1_1") (pintype "passive"))
      (node (ref "R10") (pin "2") (pinfunction "2_2") (pintype "passive"))
      (node (ref "R11") (pin "2") (pinfunction "2_2") (pintype "passive"))
    )
    (net (code "39") (name "Net-(DA1-SWC)") (class "Default")
      (node (ref "DA1") (pin "1") (pinfunction "SWC_1") (pintype "passive"))
      (node (ref "L1") (pin "2") (pinfunction "2_2") (pintype "passive"))
      (node (ref "VD1") (pin "A") (pinfunction "A_A") (pintype "passive"))
    )
    (net (code "40") (name "Net-(DA1-TC)") (class "Default")
      (node (ref "C6") (pin "1") (pinfunction "1_1") (pintype "passive"))
      (node (ref "DA1") (pin "3") (pinfunction "TC_3") (pintype "passive"))
    )
    (net (code "41") (name "Net-(DA1-VCC)") (class "Default")
      (node (ref "C7") (pin "1") (pinfunction "1_1") (pintype "passive"))
      (node (ref "C8") (pin "+") (pinfunction "+_+") (pintype "passive"))
      (node (ref "DA1") (pin "6") (pinfunction "VCC_6") (pintype "passive"))
      (node (ref "R10") (pin "1") (pinfunction "1_1") (pintype "passive"))
      (node (ref "SW1") (pin "1") (pinfunction "S_1") (pintype "passive"))
      (node (ref "SW1") (pin "4") (pinfunction "S_4") (pintype "passive"))
    )
    (net (code "42") (name "Net-(DD1-AREF)") (class "Default")
      (node (ref "C1") (pin "2") (pinfunction "2_2") (pintype "passive"))
      (node (ref "DD1") (pin "20") (pinfunction "AREF_20") (pintype "passive"))
    )
    (net (code "43") (name "Net-(DD1-PB6(XTAL1{slash}TOSC1))") (class "Default")
      (node (ref "C2") (pin "2") (pinfunction "2_2") (pintype "passive"))
      (node (ref "DD1") (pin "7") (pinfunction "PB6(XTAL1/TOSC1)_7") (pintype "bidirectional"))
      (node (ref "Z1") (pin "2") (pinfunction "2_2") (pintype "passive"))
    )
    (net (code "44") (name "Net-(DD1-PB7(XTAL2{slash}TOSC2))") (class "Default")
      (node (ref "C3") (pin "2") (pinfunction "2_2") (pintype "passive"))
      (node (ref "DD1") (pin "8") (pinfunction "PB7(XTAL2/TOSC2)_8") (pintype "bidirectional"))
      (node (ref "Z1") (pin "1") (pinfunction "1_1") (pintype "passive"))
    )
    (net (code "45") (name "Net-(HL1-C)") (class "Default")
      (node (ref "HL1") (pin "K") (pinfunction "C_K") (pintype "passive"))
      (node (ref "VT1") (pin "C") (pinfunction "C_C") (pintype "passive"))
    )
    (net (code "46") (name "Net-(HL1-PadA)") (class "Default")
      (node (ref "HL1") (pin "A") (pinfunction "A_A") (pintype "passive"))
      (node (ref "R3") (pin "1") (pinfunction "1_1") (pintype "passive"))
    )
    (net (code "47") (name "Net-(HL2-C)") (class "Default")
      (node (ref "HL2") (pin "K") (pinfunction "C_K") (pintype "passive"))
      (node (ref "VT2") (pin "C") (pinfunction "C_C") (pintype "passive"))
    )
    (net (code "48") (name "Net-(HL2-PadA)") (class "Default")
      (node (ref "HL2") (pin "A") (pinfunction "A_A") (pintype "passive"))
      (node (ref "R5") (pin "1") (pinfunction "1_1") (pintype "passive"))
    )
    (net (code "49") (name "Net-(HL3-C)") (class "Default")
      (node (ref "HL3") (pin "K") (pinfunction "C_K") (pintype "passive"))
      (node (ref "VT3") (pin "C") (pinfunction "C_C") (pintype "passive"))
    )
    (net (code "50") (name "Net-(HL3-PadA)") (class "Default")
      (node (ref "HL3") (pin "A") (pinfunction "A_A") (pintype "passive"))
      (node (ref "R7") (pin "1") (pinfunction "1_1") (pintype "passive"))
    )
    (net (code "51") (name "Net-(R2-Pad2)") (class "Default")
      (node (ref "R2") (pin "2") (pinfunction "2_2") (pintype "passive"))
      (node (ref "VT1") (pin "B") (pinfunction "B_B") (pintype "passive"))
    )
    (net (code "52") (name "Net-(R4-Pad2)") (class "Default")
      (node (ref "R4") (pin "2") (pinfunction "2_2") (pintype "passive"))
      (node (ref "VT2") (pin "B") (pinfunction "B_B") (pintype "passive"))
    )
    (net (code "53") (name "Net-(R6-Pad2)") (class "Default")
      (node (ref "R6") (pin "2") (pinfunction "2_2") (pintype "passive"))
      (node (ref "VT3") (pin "B") (pinfunction "B_B") (pintype "passive"))
    )
    (net (code "54") (name "Net-(SW1A-O)") (class "Default")
      (node (ref "SW1") (pin "3") (pinfunction "O_3") (pintype "passive"))
      (node (ref "SW1") (pin "6") (pinfunction "O_6") (pintype "passive"))
    )
    (net (code "55") (name "Net-(SW1A-P)") (class "Default")
      (node (ref "POW") (pin "1") (pinfunction "1_1") (pintype "passive"))
      (node (ref "SW1") (pin "2") (pinfunction "P_2") (pintype "passive"))
      (node (ref "SW1") (pin "5") (pinfunction "P_5") (pintype "passive"))
    )
    (net (code "56") (name "RESET") (class "Default")
      (node (ref "DD1") (pin "29") (pinfunction "PC6(/RESET)_29") (pintype "bidirectional"))
      (node (ref "ISP") (pin "5") (pinfunction "5_5") (pintype "passive"))
      (node (ref "R1") (pin "1") (pinfunction "1_1") (pintype "passive"))
    )
    (net (code "57") (name "SCK") (class "Default")
      (node (ref "DD1") (pin "17") (pinfunction "PB5(SCK)_17") (pintype "bidirectional"))
      (node (ref "DISPLAY") (pin "RES") (pinfunction "RES_RES") (pintype "bidirectional"))
      (node (ref "ISP") (pin "3") (pinfunction "3_3") (pintype "passive"))
    )
    (net (code "58") (name "SCL") (class "Default")
      (node (ref "DD1") (pin "28") (pinfunction "PC5(ADC5/SCL)_28") (pintype "bidirectional"))
      (node (ref "DD2") (pin "5") (pinfunction "SDA_5") (pintype "bidirectional"))
      (node (ref "JMEM") (pin "1") (pinfunction "1_1") (pintype "passive"))
      (node (ref "R9") (pin "1") (pinfunction "1_1") (pintype "passive"))
    )
    (net (code "59") (name "SDA") (class "Default")
      (node (ref "DD1") (pin "27") (pinfunction "PC4(ADC4/SDA)_27") (pintype "bidirectional"))
      (node (ref "DD2") (pin "6") (pinfunction "SCL_6") (pintype "input"))
      (node (ref "JMEM") (pin "2") (pinfunction "2_2") (pintype "passive"))
      (node (ref "R8") (pin "1") (pinfunction "1_1") (pintype "passive"))
    )
    (net (code "60") (name "U4") (class "Default")
      (node (ref "S35") (pin "3") (pinfunction "P_3") (pintype "passive"))
      (node (ref "S36") (pin "3") (pinfunction "P_3") (pintype "passive"))
      (node (ref "S36") (pin "4") (pinfunction "P1_4") (pintype "passive"))
      (node (ref "S37") (pin "3") (pinfunction "P_3") (pintype "passive"))
      (node (ref "S37") (pin "4") (pinfunction "P1_4") (pintype "passive"))
      (node (ref "S41") (pin "3") (pinfunction "P_3") (pintype "passive"))
      (node (ref "S41") (pin "4") (pinfunction "P1_4") (pintype "passive"))
      (node (ref "S43") (pin "3") (pinfunction "P_3") (pintype "passive"))
      (node (ref "S43") (pin "4") (pinfunction "P1_4") (pintype "passive"))
      (node (ref "S47") (pin "3") (pinfunction "P_3") (pintype "passive"))
      (node (ref "S49") (pin "3") (pinfunction "P_3") (pintype "passive"))
      (node (ref "S50") (pin "3") (pinfunction "P_3") (pintype "passive"))
      (node (ref "S50") (pin "4") (pinfunction "P1_4") (pintype "passive"))
    )
    (net (code "61") (name "U5") (class "Default")
      (node (ref "S3") (pin "3") (pinfunction "P_3") (pintype "passive"))
      (node (ref "S3") (pin "4") (pinfunction "P1_4") (pintype "passive"))
      (node (ref "S39") (pin "3") (pinfunction "P_3") (pintype "passive"))
      (node (ref "S39") (pin "4") (pinfunction "P1_4") (pintype "passive"))
      (node (ref "S42") (pin "3") (pinfunction "P_3") (pintype "passive"))
      (node (ref "S48") (pin "3") (pinfunction "P_3") (pintype "passive"))
      (node (ref "S48") (pin "4") (pinfunction "P1_4") (pintype "passive"))
      (node (ref "S55") (pin "3") (pinfunction "P_3") (pintype "passive"))
      (node (ref "S55") (pin "4") (pinfunction "P1_4") (pintype "passive"))
    )
    (net (code "62") (name "U6") (class "Default")
      (node (ref "S21") (pin "3") (pinfunction "P_3") (pintype "passive"))
      (node (ref "S25") (pin "3") (pinfunction "P_3") (pintype "passive"))
      (node (ref "S45") (pin "3") (pinfunction "P_3") (pintype "passive"))
    )
    (net (code "63") (name "U7") (class "Default")
      (node (ref "S14") (pin "3") (pinfunction "P_3") (pintype "passive"))
      (node (ref "S14") (pin "4") (pinfunction "P1_4") (pintype "passive"))
      (node (ref "S16") (pin "3") (pinfunction "P_3") (pintype "passive"))
      (node (ref "S16") (pin "4") (pinfunction "P1_4") (pintype "passive"))
      (node (ref "S17") (pin "3") (pinfunction "P_3") (pintype "passive"))
      (node (ref "S33") (pin "3") (pinfunction "P_3") (pintype "passive"))
      (node (ref "S33") (pin "4") (pinfunction "P1_4") (pintype "passive"))
      (node (ref "S38") (pin "3") (pinfunction "P_3") (pintype "passive"))
      (node (ref "S38") (pin "4") (pinfunction "P1_4") (pintype "passive"))
      (node (ref "S44") (pin "4") (pinfunction "P1_4") (pintype "passive"))
      (node (ref "S51") (pin "3") (pinfunction "P_3") (pintype "passive"))
      (node (ref "S51") (pin "4") (pinfunction "P1_4") (pintype "passive"))
      (node (ref "S57") (pin "3") (pinfunction "P_3") (pintype "passive"))
      (node (ref "S57") (pin "4") (pinfunction "P1_4") (pintype "passive"))
      (node (ref "S58") (pin "3") (pinfunction "P_3") (pintype "passive"))
      (node (ref "S58") (pin "4") (pinfunction "P1_4") (pintype "passive"))
      (node (ref "S7") (pin "3") (pinfunction "P_3") (pintype "passive"))
    )
    (net (code "64") (name "U8") (class "Default")
      (node (ref "S2") (pin "3") (pinfunction "P_3") (pintype "passive"))
      (node (ref "S22") (pin "3") (pinfunction "P_3") (pintype "passive"))
      (node (ref "S22") (pin "4") (pinfunction "P1_4") (pintype "passive"))
      (node (ref "S23") (pin "3") (pinfunction "P_3") (pintype "passive"))
      (node (ref "S23") (pin "4") (pinfunction "P1_4") (pintype "passive"))
      (node (ref "S28") (pin "3") (pinfunction "P_3") (pintype "passive"))
      (node (ref "S28") (pin "4") (pinfunction "P1_4") (pintype "passive"))
      (node (ref "S32") (pin "3") (pinfunction "P_3") (pintype "passive"))
      (node (ref "S46") (pin "3") (pinfunction "P_3") (pintype "passive"))
      (node (ref "S46") (pin "4") (pinfunction "P1_4") (pintype "passive"))
      (node (ref "S54") (pin "3") (pinfunction "P_3") (pintype "passive"))
      (node (ref "S54") (pin "4") (pinfunction "P1_4") (pintype "passive"))
    )
    (net (code "65") (name "U9") (class "Default")
      (node (ref "S13") (pin "3") (pinfunction "P_3") (pintype "passive"))
      (node (ref "S13") (pin "4") (pinfunction "P1_4") (pintype "passive"))
      (node (ref "S15") (pin "3") (pinfunction "P_3") (pintype "passive"))
      (node (ref "S15") (pin "4") (pinfunction "P1_4") (pintype "passive"))
      (node (ref "S19") (pin "4") (pinfunction "P1_4") (pintype "passive"))
      (node (ref "S27") (pin "3") (pinfunction "P_3") (pintype "passive"))
      (node (ref "S27") (pin "4") (pinfunction "P1_4") (pintype "passive"))
      (node (ref "S29") (pin "4") (pinfunction "P1_4") (pintype "passive"))
      (node (ref "S34") (pin "3") (pinfunction "P_3") (pintype "passive"))
      (node (ref "S34") (pin "4") (pinfunction "P1_4") (pintype "passive"))
      (node (ref "S40") (pin "3") (pinfunction "P_3") (pintype "passive"))
      (node (ref "S40") (pin "4") (pinfunction "P1_4") (pintype "passive"))
      (node (ref "S52") (pin "3") (pinfunction "P_3") (pintype "passive"))
      (node (ref "S52") (pin "4") (pinfunction "P1_4") (pintype "passive"))
      (node (ref "S6") (pin "3") (pinfunction "P_3") (pintype "passive"))
      (node (ref "S6") (pin "4") (pinfunction "P1_4") (pintype "passive"))
      (node (ref "S8") (pin "3") (pinfunction "P_3") (pintype "passive"))
      (node (ref "S8") (pin "4") (pinfunction "P1_4") (pintype "passive"))
    )
    (net (code "66") (name "U10") (class "Default")
      (node (ref "S1") (pin "3") (pinfunction "P_3") (pintype "passive"))
      (node (ref "S1") (pin "4") (pinfunction "P1_4") (pintype "passive"))
      (node (ref "S10") (pin "3") (pinfunction "P_3") (pintype "passive"))
      (node (ref "S10") (pin "4") (pinfunction "P1_4") (pintype "passive"))
      (node (ref "S24") (pin "4") (pinfunction "P1_4") (pintype "passive"))
      (node (ref "S4") (pin "3") (pinfunction "P_3") (pintype "passive"))
      (node (ref "S5") (pin "3") (pinfunction "P_3") (pintype "passive"))
      (node (ref "S53") (pin "3") (pinfunction "P_3") (pintype "passive"))
      (node (ref "S53") (pin "4") (pinfunction "P1_4") (pintype "passive"))
    )
    (net (code "67") (name "U11") (class "Default")
      (node (ref "S11") (pin "3") (pinfunction "P_3") (pintype "passive"))
      (node (ref "S11") (pin "4") (pinfunction "P1_4") (pintype "passive"))
      (node (ref "S12") (pin "3") (pinfunction "P_3") (pintype "passive"))
      (node (ref "S12") (pin "4") (pinfunction "P1_4") (pintype "passive"))
      (node (ref "S18") (pin "3") (pinfunction "P_3") (pintype "passive"))
      (node (ref "S18") (pin "4") (pinfunction "P1_4") (pintype "passive"))
      (node (ref "S20") (pin "3") (pinfunction "P_3") (pintype "passive"))
      (node (ref "S20") (pin "4") (pinfunction "P1_4") (pintype "passive"))
      (node (ref "S26") (pin "3") (pinfunction "P_3") (pintype "passive"))
      (node (ref "S26") (pin "4") (pinfunction "P1_4") (pintype "passive"))
      (node (ref "S30") (pin "3") (pinfunction "P_3") (pintype "passive"))
      (node (ref "S31") (pin "3") (pinfunction "P_3") (pintype "passive"))
      (node (ref "S31") (pin "4") (pinfunction "P1_4") (pintype "passive"))
      (node (ref "S56") (pin "3") (pinfunction "P_3") (pintype "passive"))
      (node (ref "S9") (pin "3") (pinfunction "P_3") (pintype "passive"))
      (node (ref "S9") (pin "4") (pinfunction "P1_4") (pintype "passive"))
    )
    (net (code "68") (name "VCC") (class "Default")
      (node (ref "C11") (pin "2") (pinfunction "2_2") (pintype "passive"))
      (node (ref "C12") (pin "+") (pinfunction "+_+") (pintype "passive"))
      (node (ref "C4") (pin "1") (pinfunction "1_1") (pintype "passive"))
      (node (ref "C5") (pin "1") (pinfunction "1_1") (pintype "passive"))
      (node (ref "DD1") (pin "18") (pinfunction "AVCC_18") (pintype "power_in"))
      (node (ref "DD1") (pin "4") (pinfunction "VCC_4") (pintype "power_in"))
      (node (ref "DD1") (pin "6") (pinfunction "VCC_6") (pintype "power_in"))
      (node (ref "DD2") (pin "8") (pinfunction "VCC_8") (pintype "power_in"))
      (node (ref "DISPLAY") (pin "VCC") (pinfunction "VCC_VCC") (pintype "bidirectional"))
      (node (ref "ISP") (pin "2") (pinfunction "2_2") (pintype "passive"))
      (node (ref "JMEM") (pin "3") (pinfunction "3_3") (pintype "passive"))
      (node (ref "KB3") (pin "1") (pinfunction "1_1") (pintype "passive"))
      (node (ref "L2") (pin "2") (pinfunction "2_2") (pintype "passive"))
      (node (ref "PINV") (pin "1") (pinfunction "1_1") (pintype "passive"))
      (node (ref "PINV") (pin "10") (pinfunction "10_10") (pintype "passive"))
      (node (ref "PINV") (pin "11") (pinfunction "11_11") (pintype "passive"))
      (node (ref "PINV") (pin "12") (pinfunction "12_12") (pintype "passive"))
      (node (ref "PINV") (pin "2") (pinfunction "2_2") (pintype "passive"))
      (node (ref "PINV") (pin "3") (pinfunction "3_3") (pintype "passive"))
      (node (ref "PINV") (pin "4") (pinfunction "4_4") (pintype "passive"))
      (node (ref "PINV") (pin "5") (pinfunction "5_5") (pintype "passive"))
      (node (ref "PINV") (pin "6") (pinfunction "6_6") (pintype "passive"))
      (node (ref "PINV") (pin "7") (pinfunction "7_7") (pintype "passive"))
      (node (ref "PINV") (pin "8") (pinfunction "8_8") (pintype "passive"))
      (node (ref "PINV") (pin "9") (pinfunction "9_9") (pintype "passive"))
      (node (ref "R1") (pin "2") (pinfunction "2_2") (pintype "passive"))
      (node (ref "R3") (pin "2") (pinfunction "2_2") (pintype "passive"))
      (node (ref "R5") (pin "2") (pinfunction "2_2") (pintype "passive"))
      (node (ref "R7") (pin "2") (pinfunction "2_2") (pintype "passive"))
      (node (ref "R8") (pin "2") (pinfunction "2_2") (pintype "passive"))
      (node (ref "R9") (pin "2") (pinfunction "2_2") (pintype "passive"))
    )
    (net (code "69") (name "unconnected-(S2-P1-Pad4)") (class "Default")
      (node (ref "S2") (pin "4") (pinfunction "P1_4") (pintype "passive"))
    )
    (net (code "70") (name "unconnected-(S4-P1-Pad4)") (class "Default")
      (node (ref "S4") (pin "4") (pinfunction "P1_4") (pintype "passive"))
    )
    (net (code "71") (name "unconnected-(S5-P1-Pad4)") (class "Default")
      (node (ref "S5") (pin "4") (pinfunction "P1_4") (pintype "passive"))
    )
    (net (code "72") (name "unconnected-(S7-P1-Pad4)") (class "Default")
      (node (ref "S7") (pin "4") (pinfunction "P1_4") (pintype "passive"))
    )
    (net (code "73") (name "unconnected-(S10-S1-Pad2)") (class "Default")
      (node (ref "S10") (pin "2") (pinfunction "S1_2") (pintype "passive"))
    )
    (net (code "74") (name "unconnected-(S12-S1-Pad2)") (class "Default")
      (node (ref "S12") (pin "2") (pinfunction "S1_2") (pintype "passive"))
    )
    (net (code "75") (name "unconnected-(S14-S1-Pad2)") (class "Default")
      (node (ref "S14") (pin "2") (pinfunction "S1_2") (pintype "passive"))
    )
    (net (code "76") (name "unconnected-(S15-S1-Pad2)") (class "Default")
      (node (ref "S15") (pin "2") (pinfunction "S1_2") (pintype "passive"))
    )
    (net (code "77") (name "unconnected-(S17-P1-Pad4)") (class "Default")
      (node (ref "S17") (pin "4") (pinfunction "P1_4") (pintype "passive"))
    )
    (net (code "78") (name "unconnected-(S19-P-Pad3)") (class "Default")
      (node (ref "S19") (pin "3") (pinfunction "P_3") (pintype "passive"))
    )
    (net (code "79") (name "unconnected-(S21-P1-Pad4)") (class "Default")
      (node (ref "S21") (pin "4") (pinfunction "P1_4") (pintype "passive"))
    )
    (net (code "80") (name "unconnected-(S21-S1-Pad2)") (class "Default")
      (node (ref "S21") (pin "2") (pinfunction "S1_2") (pintype "passive"))
    )
    (net (code "81") (name "unconnected-(S24-P-Pad3)") (class "Default")
      (node (ref "S24") (pin "3") (pinfunction "P_3") (pintype "passive"))
    )
    (net (code "82") (name "unconnected-(S24-S-Pad1)") (class "Default")
      (node (ref "S24") (pin "1") (pinfunction "S_1") (pintype "passive"))
    )
    (net (code "83") (name "unconnected-(S25-P1-Pad4)") (class "Default")
      (node (ref "S25") (pin "4") (pinfunction "P1_4") (pintype "passive"))
    )
    (net (code "84") (name "unconnected-(S26-S1-Pad2)") (class "Default")
      (node (ref "S26") (pin "2") (pinfunction "S1_2") (pintype "passive"))
    )
    (net (code "85") (name "unconnected-(S27-S1-Pad2)") (class "Default")
      (node (ref "S27") (pin "2") (pinfunction "S1_2") (pintype "passive"))
    )
    (net (code "86") (name "unconnected-(S29-P-Pad3)") (class "Default")
      (node (ref "S29") (pin "3") (pinfunction "P_3") (pintype "passive"))
    )
    (net (code "87") (name "unconnected-(S30-P1-Pad4)") (class "Default")
      (node (ref "S30") (pin "4") (pinfunction "P1_4") (pintype "passive"))
    )
    (net (code "88") (name "unconnected-(S31-S-Pad1)") (class "Default")
      (node (ref "S31") (pin "1") (pinfunction "S_1") (pintype "passive"))
    )
    (net (code "89") (name "unconnected-(S32-P1-Pad4)") (class "Default")
      (node (ref "S32") (pin "4") (pinfunction "P1_4") (pintype "passive"))
    )
    (net (code "90") (name "unconnected-(S32-S1-Pad2)") (class "Default")
      (node (ref "S32") (pin "2") (pinfunction "S1_2") (pintype "passive"))
    )
    (net (code "91") (name "unconnected-(S33-S-Pad1)") (class "Default")
      (node (ref "S33") (pin "1") (pinfunction "S_1") (pintype "passive"))
    )
    (net (code "92") (name "unconnected-(S35-P1-Pad4)") (class "Default")
      (node (ref "S35") (pin "4") (pinfunction "P1_4") (pintype "passive"))
    )
    (net (code "93") (name "unconnected-(S37-S1-Pad2)") (class "Default")
      (node (ref "S37") (pin "2") (pinfunction "S1_2") (pintype "passive"))
    )
    (net (code "94") (name "unconnected-(S38-S1-Pad2)") (class "Default")
      (node (ref "S38") (pin "2") (pinfunction "S1_2") (pintype "passive"))
    )
    (net (code "95") (name "unconnected-(S42-P1-Pad4)") (class "Default")
      (node (ref "S42") (pin "4") (pinfunction "P1_4") (pintype "passive"))
    )
    (net (code "96") (name "unconnected-(S43-S1-Pad2)") (class "Default")
      (node (ref "S43") (pin "2") (pinfunction "S1_2") (pintype "passive"))
    )
    (net (code "97") (name "unconnected-(S44-P-Pad3)") (class "Default")
      (node (ref "S44") (pin "3") (pinfunction "P_3") (pintype "passive"))
    )
    (net (code "98") (name "unconnected-(S44-S1-Pad2)") (class "Default")
      (node (ref "S44") (pin "2") (pinfunction "S1_2") (pintype "passive"))
    )
    (net (code "99") (name "unconnected-(S45-P1-Pad4)") (class "Default")
      (node (ref "S45") (pin "4") (pinfunction "P1_4") (pintype "passive"))
    )
    (net (code "100") (name "unconnected-(S47-P1-Pad4)") (class "Default")
      (node (ref "S47") (pin "4") (pinfunction "P1_4") (pintype "passive"))
    )
    (net (code "101") (name "unconnected-(S47-S1-Pad2)") (class "Default")
      (node (ref "S47") (pin "2") (pinfunction "S1_2") (pintype "passive"))
    )
    (net (code "102") (name "unconnected-(S48-S1-Pad2)") (class "Default")
      (node (ref "S48") (pin "2") (pinfunction "S1_2") (pintype "passive"))
    )
    (net (code "103") (name "unconnected-(S49-P1-Pad4)") (class "Default")
      (node (ref "S49") (pin "4") (pinfunction "P1_4") (pintype "passive"))
    )
    (net (code "104") (name "unconnected-(S49-S1-Pad2)") (class "Default")
      (node (ref "S49") (pin "2") (pinfunction "S1_2") (pintype "passive"))
    )
    (net (code "105") (name "unconnected-(S56-P1-Pad4)") (class "Default")
      (node (ref "S56") (pin "4") (pinfunction "P1_4") (pintype "passive"))
    )
  )
)
